# pyboard.net
KiCad netlist of a schematic drawn in EAGLE
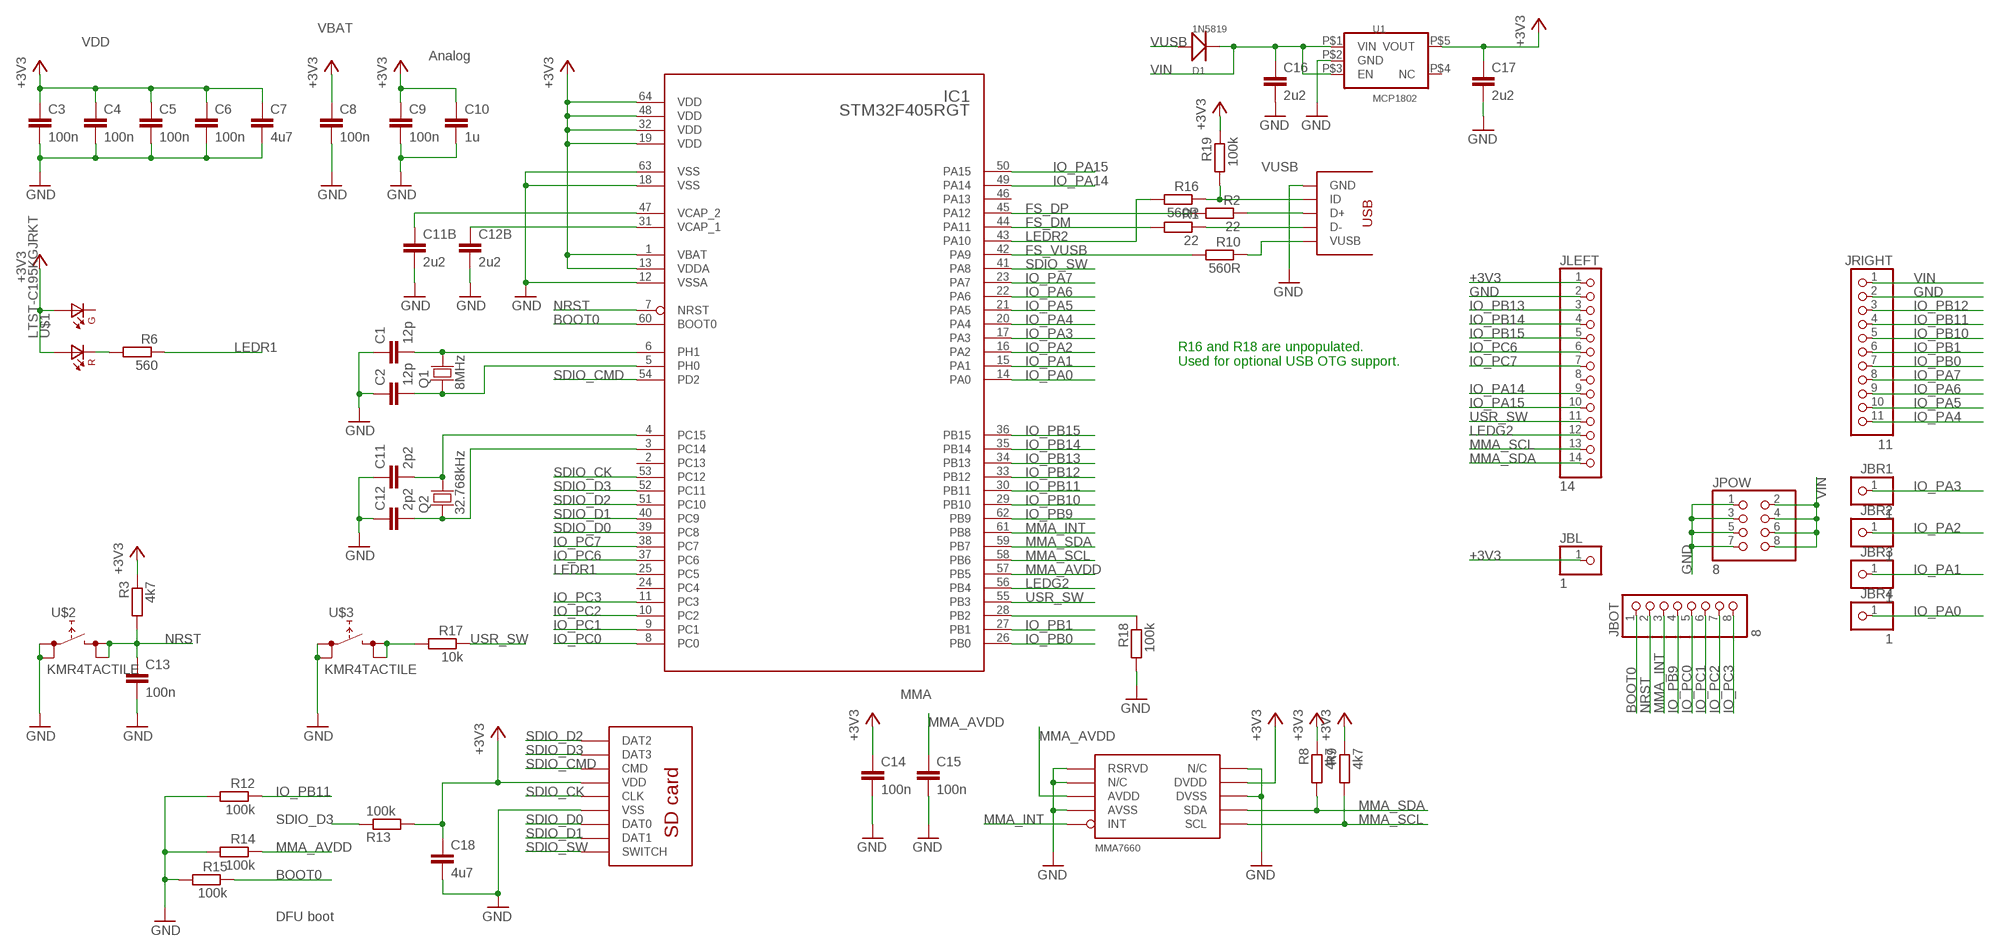
[diagram p0: schematic, sheet 1]

(export (version "E")
  (design (tool "Eeschema 10.0.6"))
  (components
    (comp (ref "C1")
      (value "12p")
      (footprint "eagle-import:C0603")
      (fields (field (name "PARTNO") "CL10C120JB8NNNC"))
      (libsource (lib "eagle-import") (part "C-EUC0603"))
    )
    (comp (ref "C2")
      (value "12p")
      (footprint "eagle-import:C0603")
      (fields (field (name "PARTNO") "CL10C120JB8NNNC"))
      (libsource (lib "eagle-import") (part "C-EUC0603"))
    )
    (comp (ref "C3")
      (value "100n")
      (footprint "eagle-import:C0603")
      (fields (field (name "PARTNO") "C0603C104J4RACTU"))
      (libsource (lib "eagle-import") (part "C-EUC0603"))
    )
    (comp (ref "C4")
      (value "100n")
      (footprint "eagle-import:C0603")
      (fields (field (name "PARTNO") "C0603C104J4RACTU"))
      (libsource (lib "eagle-import") (part "C-EUC0603"))
    )
    (comp (ref "C5")
      (value "100n")
      (footprint "eagle-import:C0603")
      (fields (field (name "PARTNO") "C0603C104J4RACTU"))
      (libsource (lib "eagle-import") (part "C-EUC0603"))
    )
    (comp (ref "C6")
      (value "100n")
      (footprint "eagle-import:C0603")
      (fields (field (name "PARTNO") "C0603C104J4RACTU"))
      (libsource (lib "eagle-import") (part "C-EUC0603"))
    )
    (comp (ref "C7")
      (value "4u7")
      (footprint "eagle-import:C0603")
      (fields (field (name "PARTNO") "CL10B475KQ8NQNC"))
      (libsource (lib "eagle-import") (part "C-EUC0603"))
    )
    (comp (ref "C8")
      (value "100n")
      (footprint "eagle-import:C0603")
      (fields (field (name "PARTNO") "C0603C104J4RACTU"))
      (libsource (lib "eagle-import") (part "C-EUC0603"))
    )
    (comp (ref "C9")
      (value "100n")
      (footprint "eagle-import:C0603")
      (fields (field (name "PARTNO") "C0603C104J4RACTU"))
      (libsource (lib "eagle-import") (part "C-EUC0603"))
    )
    (comp (ref "C10")
      (value "1u")
      (footprint "eagle-import:C0603")
      (fields (field (name "PARTNO") "YNA18B2C0G105M"))
      (libsource (lib "eagle-import") (part "C-EUC0603"))
    )
    (comp (ref "C11")
      (value "2p2")
      (footprint "eagle-import:C0603")
      (fields (field (name "PARTNO") "CL10C2R2CB8NNNC"))
      (libsource (lib "eagle-import") (part "C-EUC0603"))
    )
    (comp (ref "C11B")
      (value "2u2")
      (footprint "eagle-import:C0603")
      (fields (field (name "PARTNO") "LMK107B7225KA-T"))
      (libsource (lib "eagle-import") (part "C-EUC0603"))
    )
    (comp (ref "C12")
      (value "2p2")
      (footprint "eagle-import:C0603")
      (fields (field (name "PARTNO") "CL10C2R2CB8NNNC"))
      (libsource (lib "eagle-import") (part "C-EUC0603"))
    )
    (comp (ref "C12B")
      (value "2u2")
      (footprint "eagle-import:C0603")
      (fields (field (name "PARTNO") "LMK107B7225KA-T"))
      (libsource (lib "eagle-import") (part "C-EUC0603"))
    )
    (comp (ref "C13")
      (value "100n")
      (footprint "eagle-import:C0603")
      (fields (field (name "PARTNO") "C0603C104J4RACTU"))
      (libsource (lib "eagle-import") (part "C-EUC0603"))
    )
    (comp (ref "C14")
      (value "100n")
      (footprint "eagle-import:C0603")
      (fields (field (name "PARTNO") "C0603C104J4RACTU"))
      (libsource (lib "eagle-import") (part "C-EUC0603"))
    )
    (comp (ref "C15")
      (value "100n")
      (footprint "eagle-import:C0603")
      (fields (field (name "PARTNO") "C0603C104J4RACTU"))
      (libsource (lib "eagle-import") (part "C-EUC0603"))
    )
    (comp (ref "C16")
      (value "2u2")
      (footprint "eagle-import:C0603")
      (fields (field (name "PARTNO") "LMK107B7225KA-T"))
      (libsource (lib "eagle-import") (part "C-EUC0603"))
    )
    (comp (ref "C17")
      (value "2u2")
      (footprint "eagle-import:C0603")
      (fields (field (name "PARTNO") "LMK107B7225KA-T"))
      (libsource (lib "eagle-import") (part "C-EUC0603"))
    )
    (comp (ref "C18")
      (value "4u7")
      (footprint "eagle-import:C0603")
      (fields (field (name "PARTNO") "CL10B475KQ8NQNC"))
      (libsource (lib "eagle-import") (part "C-EUC0603"))
    )
    (comp (ref "D1")
      (value "1N5819")
      (footprint "eagle-import:SOD-123")
      (fields (field (name "PARTNO") "1N5819HW-7-F"))
      (libsource (lib "eagle-import") (part "1N5819"))
    )
    (comp (ref "IC1")
      (value "STM32F405RGT")
      (footprint "eagle-import:LQFP64")
      (fields (field (name "PARTNO") "STM32F405RGT6"))
      (libsource (lib "eagle-import") (part "STM32F405RTG"))
    )
    (comp (ref "JBL")
      (value "1")
      (footprint "eagle-import:1X01")
      (libsource (lib "eagle-import") (part "PINHD-1X1"))
    )
    (comp (ref "JBOT")
      (value "8")
      (footprint "eagle-import:1X08")
      (libsource (lib "eagle-import") (part "PINHD-1X8"))
    )
    (comp (ref "JBR1")
      (value "1")
      (footprint "eagle-import:1X01")
      (libsource (lib "eagle-import") (part "PINHD-1X1"))
    )
    (comp (ref "JBR2")
      (value "1")
      (footprint "eagle-import:1X01")
      (libsource (lib "eagle-import") (part "PINHD-1X1"))
    )
    (comp (ref "JBR3")
      (value "1")
      (footprint "eagle-import:1X01")
      (libsource (lib "eagle-import") (part "PINHD-1X1"))
    )
    (comp (ref "JBR4")
      (value "1")
      (footprint "eagle-import:1X01")
      (libsource (lib "eagle-import") (part "PINHD-1X1"))
    )
    (comp (ref "JLEFT")
      (value "14")
      (footprint "eagle-import:1X14")
      (libsource (lib "eagle-import") (part "PINHD-1X14"))
    )
    (comp (ref "JPOW")
      (value "8")
      (footprint "eagle-import:2X04")
      (libsource (lib "eagle-import") (part "PINHD-2X4"))
    )
    (comp (ref "JRIGHT")
      (value "11")
      (footprint "eagle-import:1X11")
      (libsource (lib "eagle-import") (part "PINHD-1X11"))
    )
    (comp (ref "Q1")
      (value "8MHz")
      (footprint "eagle-import:TXC-SMD-50X32")
      (fields (field (name "PARTNO") "AA-8.000MALV-T"))
      (libsource (lib "eagle-import") (part "TXC-CRYSTAL50X32"))
    )
    (comp (ref "Q2")
      (value "32.768kHz")
      (footprint "eagle-import:TXC-SMD-32X15")
      (fields (field (name "PARTNO") "ABS07-120-32.768KHZ-T"))
      (libsource (lib "eagle-import") (part "TXC-CRYSTAL32X15"))
    )
    (comp (ref "R1")
      (value "22")
      (footprint "eagle-import:R0603")
      (fields (field (name "PARTNO") "MCR03ERTJ220"))
      (libsource (lib "eagle-import") (part "R-EU_R0603"))
    )
    (comp (ref "R2")
      (value "22")
      (footprint "eagle-import:R0603")
      (fields (field (name "PARTNO") "MCR03ERTJ220"))
      (libsource (lib "eagle-import") (part "R-EU_R0603"))
    )
    (comp (ref "R3")
      (value "4k7")
      (footprint "eagle-import:R0603")
      (fields (field (name "PARTNO") "RC0603JR-074K7L"))
      (libsource (lib "eagle-import") (part "R-EU_R0603"))
    )
    (comp (ref "R6")
      (value "560")
      (footprint "eagle-import:R0603")
      (fields (field (name "PARTNO") "RC0603FR-07560RL"))
      (libsource (lib "eagle-import") (part "R-EU_R0603"))
    )
    (comp (ref "R8")
      (value "4k7")
      (footprint "eagle-import:R0603")
      (fields (field (name "PARTNO") "RC0603JR-074K7L"))
      (libsource (lib "eagle-import") (part "R-EU_R0603"))
    )
    (comp (ref "R9")
      (value "4k7")
      (footprint "eagle-import:R0603")
      (fields (field (name "PARTNO") "RC0603JR-074K7L"))
      (libsource (lib "eagle-import") (part "R-EU_R0603"))
    )
    (comp (ref "R10")
      (value "560R")
      (footprint "eagle-import:R0603")
      (fields (field (name "PARTNO") "RC0603FR-07560RL"))
      (libsource (lib "eagle-import") (part "R-EU_R0603"))
    )
    (comp (ref "R12")
      (value "100k")
      (footprint "eagle-import:R0603")
      (fields (field (name "PARTNO") "RC0603JR-07100KL"))
      (libsource (lib "eagle-import") (part "R-EU_R0603"))
    )
    (comp (ref "R13")
      (value "100k")
      (footprint "eagle-import:R0603")
      (fields (field (name "PARTNO") "RC0603JR-07100KL"))
      (libsource (lib "eagle-import") (part "R-EU_R0603"))
    )
    (comp (ref "R14")
      (value "100k")
      (footprint "eagle-import:R0603")
      (fields (field (name "PARTNO") "RC0603JR-07100KL"))
      (libsource (lib "eagle-import") (part "R-EU_R0603"))
    )
    (comp (ref "R15")
      (value "100k")
      (footprint "eagle-import:R0603")
      (fields (field (name "PARTNO") "RC0603JR-07100KL"))
      (libsource (lib "eagle-import") (part "R-EU_R0603"))
    )
    (comp (ref "R16")
      (value "560R")
      (footprint "eagle-import:R0603")
      (fields (field (name "PARTNO") "RC0603FR-07560RL"))
      (libsource (lib "eagle-import") (part "R-EU_R0603"))
    )
    (comp (ref "R17")
      (value "10k")
      (footprint "eagle-import:R0603")
      (fields (field (name "PARTNO") "RC0603JR-0710KL"))
      (libsource (lib "eagle-import") (part "R-EU_R0603"))
    )
    (comp (ref "R18")
      (value "100k")
      (footprint "eagle-import:R0603")
      (fields (field (name "PARTNO") "RC0603JR-07100KL"))
      (libsource (lib "eagle-import") (part "R-EU_R0603"))
    )
    (comp (ref "R19")
      (value "100k")
      (footprint "eagle-import:R0603")
      (fields (field (name "PARTNO") "RC0603JR-07100KL"))
      (libsource (lib "eagle-import") (part "R-EU_R0603"))
    )
    (comp (ref "U$1")
      (value "LTST-C195KGJRKT")
      (footprint "eagle-import:LTST-BILED-15X16")
      (libsource (lib "eagle-import") (part "LTST-C195KGJRKT"))
    )
    (comp (ref "U$2")
      (value "KMR4TACTILE")
      (footprint "eagle-import:KMR4SWITCH")
      (fields (field (name "PARTNO") "KMR442G LFS"))
      (libsource (lib "eagle-import") (part "KMR4TACTILE"))
    )
    (comp (ref "U$3")
      (value "KMR4TACTILE")
      (footprint "eagle-import:KMR4SWITCH")
      (fields (field (name "PARTNO") "KMR442G LFS"))
      (libsource (lib "eagle-import") (part "KMR4TACTILE"))
    )
    (comp (ref "U$4")
      (value "MOLEX-SD-105027")
      (footprint "eagle-import:MOLEX-SD-105027-PKG")
      (fields (field (name "PARTNO") "1050270001"))
      (libsource (lib "eagle-import") (part "MOLEX-SD-105027"))
    )
    (comp (ref "U$5")
      (value "MMA7660")
      (footprint "eagle-import:DFN10")
      (fields (field (name "PARTNO") "MMA7660FCR1"))
      (libsource (lib "eagle-import") (part "MMA7660"))
    )
    (comp (ref "U$7")
      (value "USB-MICRO-AB")
      (footprint "eagle-import:HRS-USB-ZX62D-AB-5P8-PKG")
      (fields (field (name "PARTNO") "ZX62D-AB-5P8"))
      (libsource (lib "eagle-import") (part "USB-MICRO-AB"))
    )
    (comp (ref "U1")
      (value "MCP1802")
      (footprint "eagle-import:SOT-23-5")
      (fields (field (name "PARTNO") "MCP1802T-3302I/OT"))
      (libsource (lib "eagle-import") (part "MCP1802"))
    )
  )
  (nets
    (net (code "1") (name "+3V3") (class "Default")
      (node (ref "C10") (pin "1") (pinfunction "1_1") (pintype "passive"))
      (node (ref "C14") (pin "1") (pinfunction "1_1") (pintype "passive"))
      (node (ref "C17") (pin "1") (pinfunction "1_1") (pintype "passive"))
      (node (ref "C18") (pin "1") (pinfunction "1_1") (pintype "passive"))
      (node (ref "C3") (pin "1") (pinfunction "1_1") (pintype "passive"))
      (node (ref "C4") (pin "1") (pinfunction "1_1") (pintype "passive"))
      (node (ref "C5") (pin "1") (pinfunction "1_1") (pintype "passive"))
      (node (ref "C6") (pin "1") (pinfunction "1_1") (pintype "passive"))
      (node (ref "C7") (pin "1") (pinfunction "1_1") (pintype "passive"))
      (node (ref "C8") (pin "1") (pinfunction "1_1") (pintype "passive"))
      (node (ref "C9") (pin "1") (pinfunction "1_1") (pintype "passive"))
      (node (ref "IC1") (pin "1") (pinfunction "VBAT_1") (pintype "power_in"))
      (node (ref "IC1") (pin "13") (pinfunction "VDDA_13") (pintype "power_in"))
      (node (ref "IC1") (pin "19") (pinfunction "VDD_19") (pintype "power_in"))
      (node (ref "IC1") (pin "32") (pinfunction "VDD_32") (pintype "power_in"))
      (node (ref "IC1") (pin "48") (pinfunction "VDD_48") (pintype "power_in"))
      (node (ref "IC1") (pin "64") (pinfunction "VDD_64") (pintype "power_in"))
      (node (ref "JBL") (pin "1") (pinfunction "1_1") (pintype "passive"))
      (node (ref "JLEFT") (pin "1") (pinfunction "1_1") (pintype "passive"))
      (node (ref "R13") (pin "2") (pinfunction "2_2") (pintype "passive"))
      (node (ref "R19") (pin "1") (pinfunction "1_1") (pintype "passive"))
      (node (ref "R3") (pin "1") (pinfunction "1_1") (pintype "passive"))
      (node (ref "R8") (pin "1") (pinfunction "1_1") (pintype "passive"))
      (node (ref "R9") (pin "1") (pinfunction "1_1") (pintype "passive"))
      (node (ref "U$1") (pin "P$1") (pinfunction "A1_P$1") (pintype "passive"))
      (node (ref "U$1") (pin "P$2") (pinfunction "A2_P$2") (pintype "passive"))
      (node (ref "U$4") (pin "P$4") (pinfunction "VDD_P$4") (pintype "bidirectional"))
      (node (ref "U$5") (pin "P$9") (pinfunction "DVDD_P$9") (pintype "power_in"))
      (node (ref "U1") (pin "P$5") (pinfunction "VOUT_P$5") (pintype "power_in"))
    )
    (net (code "2") (name "/BOOT0") (class "Default")
      (node (ref "IC1") (pin "60") (pinfunction "BOOT0_60") (pintype "bidirectional"))
      (node (ref "JBOT") (pin "1") (pinfunction "1_1") (pintype "passive"))
      (node (ref "R15") (pin "1") (pinfunction "1_1") (pintype "passive"))
    )
    (net (code "3") (name "/FS_DM") (class "Default")
      (node (ref "IC1") (pin "44") (pinfunction "PA11_44") (pintype "bidirectional"))
      (node (ref "R1") (pin "2") (pinfunction "2_2") (pintype "passive"))
    )
    (net (code "4") (name "/FS_DP") (class "Default")
      (node (ref "IC1") (pin "45") (pinfunction "PA12_45") (pintype "bidirectional"))
      (node (ref "R2") (pin "2") (pinfunction "2_2") (pintype "passive"))
    )
    (net (code "5") (name "/FS_VUSB") (class "Default")
      (node (ref "IC1") (pin "42") (pinfunction "PA9_42") (pintype "bidirectional"))
      (node (ref "R10") (pin "2") (pinfunction "2_2") (pintype "passive"))
    )
    (net (code "6") (name "/IO_PA0") (class "Default")
      (node (ref "IC1") (pin "14") (pinfunction "PA0_14") (pintype "bidirectional"))
      (node (ref "JBR4") (pin "1") (pinfunction "1_1") (pintype "passive"))
    )
    (net (code "7") (name "/IO_PA1") (class "Default")
      (node (ref "IC1") (pin "15") (pinfunction "PA1_15") (pintype "bidirectional"))
      (node (ref "JBR3") (pin "1") (pinfunction "1_1") (pintype "passive"))
    )
    (net (code "8") (name "/IO_PA2") (class "Default")
      (node (ref "IC1") (pin "16") (pinfunction "PA2_16") (pintype "bidirectional"))
      (node (ref "JBR2") (pin "1") (pinfunction "1_1") (pintype "passive"))
    )
    (net (code "9") (name "/IO_PA3") (class "Default")
      (node (ref "IC1") (pin "17") (pinfunction "PA3_17") (pintype "bidirectional"))
      (node (ref "JBR1") (pin "1") (pinfunction "1_1") (pintype "passive"))
    )
    (net (code "10") (name "/IO_PA4") (class "Default")
      (node (ref "IC1") (pin "20") (pinfunction "PA4_20") (pintype "bidirectional"))
      (node (ref "JRIGHT") (pin "11") (pinfunction "11_11") (pintype "passive"))
    )
    (net (code "11") (name "/IO_PA5") (class "Default")
      (node (ref "IC1") (pin "21") (pinfunction "PA5_21") (pintype "bidirectional"))
      (node (ref "JRIGHT") (pin "10") (pinfunction "10_10") (pintype "passive"))
    )
    (net (code "12") (name "/IO_PA6") (class "Default")
      (node (ref "IC1") (pin "22") (pinfunction "PA6_22") (pintype "bidirectional"))
      (node (ref "JRIGHT") (pin "9") (pinfunction "9_9") (pintype "passive"))
    )
    (net (code "13") (name "/IO_PA7") (class "Default")
      (node (ref "IC1") (pin "23") (pinfunction "PA7_23") (pintype "bidirectional"))
      (node (ref "JRIGHT") (pin "8") (pinfunction "8_8") (pintype "passive"))
    )
    (net (code "14") (name "/IO_PA14") (class "Default")
      (node (ref "IC1") (pin "49") (pinfunction "PA14_49") (pintype "bidirectional"))
      (node (ref "JLEFT") (pin "9") (pinfunction "9_9") (pintype "passive"))
    )
    (net (code "15") (name "/IO_PA15") (class "Default")
      (node (ref "IC1") (pin "50") (pinfunction "PA15_50") (pintype "bidirectional"))
      (node (ref "JLEFT") (pin "10") (pinfunction "10_10") (pintype "passive"))
    )
    (net (code "16") (name "/IO_PB0") (class "Default")
      (node (ref "IC1") (pin "26") (pinfunction "PB0_26") (pintype "bidirectional"))
      (node (ref "JRIGHT") (pin "7") (pinfunction "7_7") (pintype "passive"))
    )
    (net (code "17") (name "/IO_PB1") (class "Default")
      (node (ref "IC1") (pin "27") (pinfunction "PB1_27") (pintype "bidirectional"))
      (node (ref "JRIGHT") (pin "6") (pinfunction "6_6") (pintype "passive"))
    )
    (net (code "18") (name "/IO_PB9") (class "Default")
      (node (ref "IC1") (pin "62") (pinfunction "PB9_62") (pintype "bidirectional"))
      (node (ref "JBOT") (pin "4") (pinfunction "4_4") (pintype "passive"))
    )
    (net (code "19") (name "/IO_PB10") (class "Default")
      (node (ref "IC1") (pin "29") (pinfunction "PB10_29") (pintype "bidirectional"))
      (node (ref "JRIGHT") (pin "5") (pinfunction "5_5") (pintype "passive"))
    )
    (net (code "20") (name "/IO_PB11") (class "Default")
      (node (ref "IC1") (pin "30") (pinfunction "PB11_30") (pintype "bidirectional"))
      (node (ref "JRIGHT") (pin "4") (pinfunction "4_4") (pintype "passive"))
      (node (ref "R12") (pin "1") (pinfunction "1_1") (pintype "passive"))
    )
    (net (code "21") (name "/IO_PB12") (class "Default")
      (node (ref "IC1") (pin "33") (pinfunction "PB12_33") (pintype "bidirectional"))
      (node (ref "JRIGHT") (pin "3") (pinfunction "3_3") (pintype "passive"))
    )
    (net (code "22") (name "/IO_PB13") (class "Default")
      (node (ref "IC1") (pin "34") (pinfunction "PB13_34") (pintype "bidirectional"))
      (node (ref "JLEFT") (pin "3") (pinfunction "3_3") (pintype "passive"))
    )
    (net (code "23") (name "/IO_PB14") (class "Default")
      (node (ref "IC1") (pin "35") (pinfunction "PB14_35") (pintype "bidirectional"))
      (node (ref "JLEFT") (pin "4") (pinfunction "4_4") (pintype "passive"))
    )
    (net (code "24") (name "/IO_PB15") (class "Default")
      (node (ref "IC1") (pin "36") (pinfunction "PB15_36") (pintype "bidirectional"))
      (node (ref "JLEFT") (pin "5") (pinfunction "5_5") (pintype "passive"))
    )
    (net (code "25") (name "/IO_PC0") (class "Default")
      (node (ref "IC1") (pin "8") (pinfunction "PC0_8") (pintype "bidirectional"))
      (node (ref "JBOT") (pin "5") (pinfunction "5_5") (pintype "passive"))
    )
    (net (code "26") (name "/IO_PC1") (class "Default")
      (node (ref "IC1") (pin "9") (pinfunction "PC1_9") (pintype "bidirectional"))
      (node (ref "JBOT") (pin "6") (pinfunction "6_6") (pintype "passive"))
    )
    (net (code "27") (name "/IO_PC2") (class "Default")
      (node (ref "IC1") (pin "10") (pinfunction "PC2_10") (pintype "bidirectional"))
      (node (ref "JBOT") (pin "7") (pinfunction "7_7") (pintype "passive"))
    )
    (net (code "28") (name "/IO_PC3") (class "Default")
      (node (ref "IC1") (pin "11") (pinfunction "PC3_11") (pintype "bidirectional"))
      (node (ref "JBOT") (pin "8") (pinfunction "8_8") (pintype "passive"))
    )
    (net (code "29") (name "/IO_PC6") (class "Default")
      (node (ref "IC1") (pin "37") (pinfunction "PC6_37") (pintype "bidirectional"))
      (node (ref "JLEFT") (pin "6") (pinfunction "6_6") (pintype "passive"))
    )
    (net (code "30") (name "/IO_PC7") (class "Default")
      (node (ref "IC1") (pin "38") (pinfunction "PC7_38") (pintype "bidirectional"))
      (node (ref "JLEFT") (pin "7") (pinfunction "7_7") (pintype "passive"))
    )
    (net (code "31") (name "/LEDG2") (class "Default")
      (node (ref "IC1") (pin "56") (pinfunction "PB4_56") (pintype "bidirectional"))
      (node (ref "JLEFT") (pin "12") (pinfunction "12_12") (pintype "passive"))
    )
    (net (code "32") (name "/LEDR1") (class "Default")
      (node (ref "IC1") (pin "25") (pinfunction "PC5_25") (pintype "bidirectional"))
      (node (ref "R6") (pin "1") (pinfunction "1_1") (pintype "passive"))
    )
    (net (code "33") (name "/LEDR2") (class "Default")
      (node (ref "IC1") (pin "43") (pinfunction "PA10_43") (pintype "bidirectional"))
      (node (ref "R16") (pin "2") (pinfunction "2_2") (pintype "passive"))
    )
    (net (code "34") (name "/MMA_AVDD") (class "Default")
      (node (ref "C15") (pin "1") (pinfunction "1_1") (pintype "passive"))
      (node (ref "IC1") (pin "57") (pinfunction "PB5_57") (pintype "bidirectional"))
      (node (ref "R14") (pin "1") (pinfunction "1_1") (pintype "passive"))
      (node (ref "U$5") (pin "P$3") (pinfunction "AVDD_P$3") (pintype "power_in"))
    )
    (net (code "35") (name "/MMA_INT") (class "Default")
      (node (ref "IC1") (pin "61") (pinfunction "PB8_61") (pintype "bidirectional"))
      (node (ref "JBOT") (pin "3") (pinfunction "3_3") (pintype "passive"))
      (node (ref "U$5") (pin "P$5") (pinfunction "INT_P$5") (pintype "output"))
    )
    (net (code "36") (name "/MMA_SCL") (class "Default")
      (node (ref "IC1") (pin "58") (pinfunction "PB6_58") (pintype "bidirectional"))
      (node (ref "JLEFT") (pin "13") (pinfunction "13_13") (pintype "passive"))
      (node (ref "R9") (pin "2") (pinfunction "2_2") (pintype "passive"))
      (node (ref "U$5") (pin "P$6") (pinfunction "SCL_P$6") (pintype "input"))
    )
    (net (code "37") (name "/MMA_SDA") (class "Default")
      (node (ref "IC1") (pin "59") (pinfunction "PB7_59") (pintype "bidirectional"))
      (node (ref "JLEFT") (pin "14") (pinfunction "14_14") (pintype "passive"))
      (node (ref "R8") (pin "2") (pinfunction "2_2") (pintype "passive"))
      (node (ref "U$5") (pin "P$7") (pinfunction "SDA_P$7") (pintype "output"))
    )
    (net (code "38") (name "/NRST") (class "Default")
      (node (ref "C13") (pin "1") (pinfunction "1_1") (pintype "passive"))
      (node (ref "IC1") (pin "7") (pinfunction "NRST_7") (pintype "input"))
      (node (ref "JBOT") (pin "2") (pinfunction "2_2") (pintype "passive"))
      (node (ref "R3") (pin "2") (pinfunction "2_2") (pintype "passive"))
      (node (ref "U$2") (pin "P$3") (pinfunction "1_P$3") (pintype "passive"))
      (node (ref "U$2") (pin "P$4") (pinfunction "1_P$4") (pintype "passive"))
    )
    (net (code "39") (name "/SDIO_CK") (class "Default")
      (node (ref "IC1") (pin "53") (pinfunction "PC12_53") (pintype "bidirectional"))
      (node (ref "U$4") (pin "P$5") (pinfunction "CLK_P$5") (pintype "bidirectional"))
    )
    (net (code "40") (name "/SDIO_CMD") (class "Default")
      (node (ref "IC1") (pin "54") (pinfunction "PD2_54") (pintype "bidirectional"))
      (node (ref "U$4") (pin "P$3") (pinfunction "CMD_P$3") (pintype "bidirectional"))
    )
    (net (code "41") (name "/SDIO_D0") (class "Default")
      (node (ref "IC1") (pin "39") (pinfunction "PC8_39") (pintype "bidirectional"))
      (node (ref "U$4") (pin "P$7") (pinfunction "DAT0_P$7") (pintype "bidirectional"))
    )
    (net (code "42") (name "/SDIO_D1") (class "Default")
      (node (ref "IC1") (pin "40") (pinfunction "PC9_40") (pintype "bidirectional"))
      (node (ref "U$4") (pin "P$8") (pinfunction "DAT1_P$8") (pintype "bidirectional"))
    )
    (net (code "43") (name "/SDIO_D2") (class "Default")
      (node (ref "IC1") (pin "51") (pinfunction "PC10_51") (pintype "bidirectional"))
      (node (ref "U$4") (pin "P$1") (pinfunction "DAT2_P$1") (pintype "bidirectional"))
    )
    (net (code "44") (name "/SDIO_D3") (class "Default")
      (node (ref "IC1") (pin "52") (pinfunction "PC11_52") (pintype "bidirectional"))
      (node (ref "R13") (pin "1") (pinfunction "1_1") (pintype "passive"))
      (node (ref "U$4") (pin "P$2") (pinfunction "DAT3_P$2") (pintype "bidirectional"))
    )
    (net (code "45") (name "/SDIO_SW") (class "Default")
      (node (ref "IC1") (pin "41") (pinfunction "PA8_41") (pintype "bidirectional"))
      (node (ref "U$4") (pin "G$1") (pinfunction "SWITCH_G$1") (pintype "bidirectional"))
    )
    (net (code "46") (name "/USR_SW") (class "Default")
      (node (ref "IC1") (pin "55") (pinfunction "PB3_55") (pintype "bidirectional"))
      (node (ref "JLEFT") (pin "11") (pinfunction "11_11") (pintype "passive"))
      (node (ref "R17") (pin "1") (pinfunction "1_1") (pintype "passive"))
    )
    (net (code "47") (name "/VIN") (class "Default")
      (node (ref "C16") (pin "1") (pinfunction "1_1") (pintype "passive"))
      (node (ref "D1") (pin "K") (pinfunction "K_K") (pintype "passive"))
      (node (ref "JPOW") (pin "2") (pinfunction "2_2") (pintype "passive"))
      (node (ref "JPOW") (pin "4") (pinfunction "4_4") (pintype "passive"))
      (node (ref "JPOW") (pin "6") (pinfunction "6_6") (pintype "passive"))
      (node (ref "JPOW") (pin "8") (pinfunction "8_8") (pintype "passive"))
      (node (ref "JRIGHT") (pin "1") (pinfunction "1_1") (pintype "passive"))
      (node (ref "U1") (pin "P$1") (pinfunction "VIN_P$1") (pintype "power_in"))
      (node (ref "U1") (pin "P$3") (pinfunction "EN_P$3") (pintype "input"))
    )
    (net (code "48") (name "/VUSB") (class "Default")
      (node (ref "D1") (pin "A") (pinfunction "A_A") (pintype "passive"))
      (node (ref "R10") (pin "1") (pinfunction "1_1") (pintype "passive"))
      (node (ref "U$7") (pin "P$1") (pinfunction "VUSB_P$1") (pintype "power_in"))
    )
    (net (code "49") (name "GND") (class "Default")
      (node (ref "C1") (pin "1") (pinfunction "1_1") (pintype "passive"))
      (node (ref "C10") (pin "2") (pinfunction "2_2") (pintype "passive"))
      (node (ref "C11") (pin "1") (pinfunction "1_1") (pintype "passive"))
      (node (ref "C11B") (pin "2") (pinfunction "2_2") (pintype "passive"))
      (node (ref "C12") (pin "1") (pinfunction "1_1") (pintype "passive"))
      (node (ref "C12B") (pin "2") (pinfunction "2_2") (pintype "passive"))
      (node (ref "C13") (pin "2") (pinfunction "2_2") (pintype "passive"))
      (node (ref "C14") (pin "2") (pinfunction "2_2") (pintype "passive"))
      (node (ref "C15") (pin "2") (pinfunction "2_2") (pintype "passive"))
      (node (ref "C16") (pin "2") (pinfunction "2_2") (pintype "passive"))
      (node (ref "C17") (pin "2") (pinfunction "2_2") (pintype "passive"))
      (node (ref "C18") (pin "2") (pinfunction "2_2") (pintype "passive"))
      (node (ref "C2") (pin "1") (pinfunction "1_1") (pintype "passive"))
      (node (ref "C3") (pin "2") (pinfunction "2_2") (pintype "passive"))
      (node (ref "C4") (pin "2") (pinfunction "2_2") (pintype "passive"))
      (node (ref "C5") (pin "2") (pinfunction "2_2") (pintype "passive"))
      (node (ref "C6") (pin "2") (pinfunction "2_2") (pintype "passive"))
      (node (ref "C7") (pin "2") (pinfunction "2_2") (pintype "passive"))
      (node (ref "C8") (pin "2") (pinfunction "2_2") (pintype "passive"))
      (node (ref "C9") (pin "2") (pinfunction "2_2") (pintype "passive"))
      (node (ref "IC1") (pin "12") (pinfunction "VSSA_12") (pintype "power_in"))
      (node (ref "IC1") (pin "18") (pinfunction "VSS_18") (pintype "power_in"))
      (node (ref "IC1") (pin "63") (pinfunction "VSS_63") (pintype "power_in"))
      (node (ref "JLEFT") (pin "2") (pinfunction "2_2") (pintype "passive"))
      (node (ref "JPOW") (pin "1") (pinfunction "1_1") (pintype "passive"))
      (node (ref "JPOW") (pin "3") (pinfunction "3_3") (pintype "passive"))
      (node (ref "JPOW") (pin "5") (pinfunction "5_5") (pintype "passive"))
      (node (ref "JPOW") (pin "7") (pinfunction "7_7") (pintype "passive"))
      (node (ref "JRIGHT") (pin "2") (pinfunction "2_2") (pintype "passive"))
      (node (ref "R12") (pin "2") (pinfunction "2_2") (pintype "passive"))
      (node (ref "R14") (pin "2") (pinfunction "2_2") (pintype "passive"))
      (node (ref "R15") (pin "2") (pinfunction "2_2") (pintype "passive"))
      (node (ref "R18") (pin "2") (pinfunction "2_2") (pintype "passive"))
      (node (ref "U$2") (pin "P$1") (pinfunction "0_P$1") (pintype "passive"))
      (node (ref "U$2") (pin "P$2") (pinfunction "0_P$2") (pintype "passive"))
      (node (ref "U$3") (pin "P$1") (pinfunction "0_P$1") (pintype "passive"))
      (node (ref "U$3") (pin "P$2") (pinfunction "0_P$2") (pintype "passive"))
      (node (ref "U$4") (pin "P$6") (pinfunction "VSS_P$6") (pintype "bidirectional"))
      (node (ref "U$5") (pin "P$1") (pinfunction "RSRVD_P$1") (pintype "input"))
      (node (ref "U$5") (pin "P$10") (pinfunction "N/C_P$10") (pintype "input"))
      (node (ref "U$5") (pin "P$2") (pinfunction "N/C_P$2") (pintype "input"))
      (node (ref "U$5") (pin "P$4") (pinfunction "AVSS_P$4") (pintype "power_in"))
      (node (ref "U$5") (pin "P$8") (pinfunction "DVSS_P$8") (pintype "power_in"))
      (node (ref "U$7") (pin "P$5") (pinfunction "GND_P$5") (pintype "power_in"))
      (node (ref "U1") (pin "P$2") (pinfunction "GND_P$2") (pintype "power_in"))
    )
    (net (code "50") (name "Net-(IC1-PB2)") (class "Default")
      (node (ref "IC1") (pin "28") (pinfunction "PB2_28") (pintype "bidirectional"))
      (node (ref "R18") (pin "1") (pinfunction "1_1") (pintype "passive"))
    )
    (net (code "51") (name "Net-(IC1-PC14)") (class "Default")
      (node (ref "C12") (pin "2") (pinfunction "2_2") (pintype "passive"))
      (node (ref "IC1") (pin "3") (pinfunction "PC14_3") (pintype "bidirectional"))
      (node (ref "Q2") (pin "P$1") (pinfunction "P$1_P$1") (pintype "passive"))
    )
    (net (code "52") (name "Net-(IC1-PC15)") (class "Default")
      (node (ref "C11") (pin "2") (pinfunction "2_2") (pintype "passive"))
      (node (ref "IC1") (pin "4") (pinfunction "PC15_4") (pintype "bidirectional"))
      (node (ref "Q2") (pin "P$2") (pinfunction "P$2_P$2") (pintype "passive"))
    )
    (net (code "53") (name "Net-(IC1-PH0)") (class "Default")
      (node (ref "C2") (pin "2") (pinfunction "2_2") (pintype "passive"))
      (node (ref "IC1") (pin "5") (pinfunction "PH0_5") (pintype "bidirectional"))
      (node (ref "Q1") (pin "P$1") (pinfunction "P$1_P$1") (pintype "passive"))
    )
    (net (code "54") (name "Net-(IC1-PH1)") (class "Default")
      (node (ref "C1") (pin "2") (pinfunction "2_2") (pintype "passive"))
      (node (ref "IC1") (pin "6") (pinfunction "PH1_6") (pintype "bidirectional"))
      (node (ref "Q1") (pin "P$2") (pinfunction "P$2_P$2") (pintype "passive"))
    )
    (net (code "55") (name "Net-(IC1-VCAP_1)") (class "Default")
      (node (ref "C12B") (pin "1") (pinfunction "1_1") (pintype "passive"))
      (node (ref "IC1") (pin "31") (pinfunction "VCAP_1_31") (pintype "passive"))
    )
    (net (code "56") (name "Net-(IC1-VCAP_2)") (class "Default")
      (node (ref "C11B") (pin "1") (pinfunction "1_1") (pintype "passive"))
      (node (ref "IC1") (pin "47") (pinfunction "VCAP_2_47") (pintype "passive"))
    )
    (net (code "57") (name "Net-(R17-Pad2)") (class "Default")
      (node (ref "R17") (pin "2") (pinfunction "2_2") (pintype "passive"))
      (node (ref "U$3") (pin "P$3") (pinfunction "1_P$3") (pintype "passive"))
      (node (ref "U$3") (pin "P$4") (pinfunction "1_P$4") (pintype "passive"))
    )
    (net (code "58") (name "Net-(U$1-K2)") (class "Default")
      (node (ref "R6") (pin "2") (pinfunction "2_2") (pintype "passive"))
      (node (ref "U$1") (pin "P$4") (pinfunction "K2_P$4") (pintype "passive"))
    )
    (net (code "59") (name "Net-(U$7-D+)") (class "Default")
      (node (ref "R2") (pin "1") (pinfunction "1_1") (pintype "passive"))
      (node (ref "U$7") (pin "P$3") (pinfunction "D+_P$3") (pintype "bidirectional"))
    )
    (net (code "60") (name "Net-(U$7-D-)") (class "Default")
      (node (ref "R1") (pin "1") (pinfunction "1_1") (pintype "passive"))
      (node (ref "U$7") (pin "P$2") (pinfunction "D-_P$2") (pintype "bidirectional"))
    )
    (net (code "61") (name "Net-(U$7-ID)") (class "Default")
      (node (ref "R16") (pin "1") (pinfunction "1_1") (pintype "passive"))
      (node (ref "R19") (pin "2") (pinfunction "2_2") (pintype "passive"))
      (node (ref "U$7") (pin "P$4") (pinfunction "ID_P$4") (pintype "bidirectional"))
    )
    (net (code "62") (name "unconnected-(IC1-PA13-Pad46)") (class "Default")
      (node (ref "IC1") (pin "46") (pinfunction "PA13_46") (pintype "bidirectional"))
    )
    (net (code "63") (name "unconnected-(IC1-PC4-Pad24)") (class "Default")
      (node (ref "IC1") (pin "24") (pinfunction "PC4_24") (pintype "bidirectional"))
    )
    (net (code "64") (name "unconnected-(IC1-PC13-Pad2)") (class "Default")
      (node (ref "IC1") (pin "2") (pinfunction "PC13_2") (pintype "bidirectional"))
    )
    (net (code "65") (name "unconnected-(JLEFT-Pad8)") (class "Default")
      (node (ref "JLEFT") (pin "8") (pinfunction "8_8") (pintype "passive"))
    )
    (net (code "66") (name "unconnected-(U$1-K1-PadP$3)") (class "Default")
      (node (ref "U$1") (pin "P$3") (pinfunction "K1_P$3") (pintype "passive"))
    )
    (net (code "67") (name "unconnected-(U1-NC-PadP$4)") (class "Default")
      (node (ref "U1") (pin "P$4") (pinfunction "NC_P$4") (pintype "no_connect"))
    )
  )
)
